# 7seg-weather.net
KiCad netlist of a schematic drawn in EAGLE
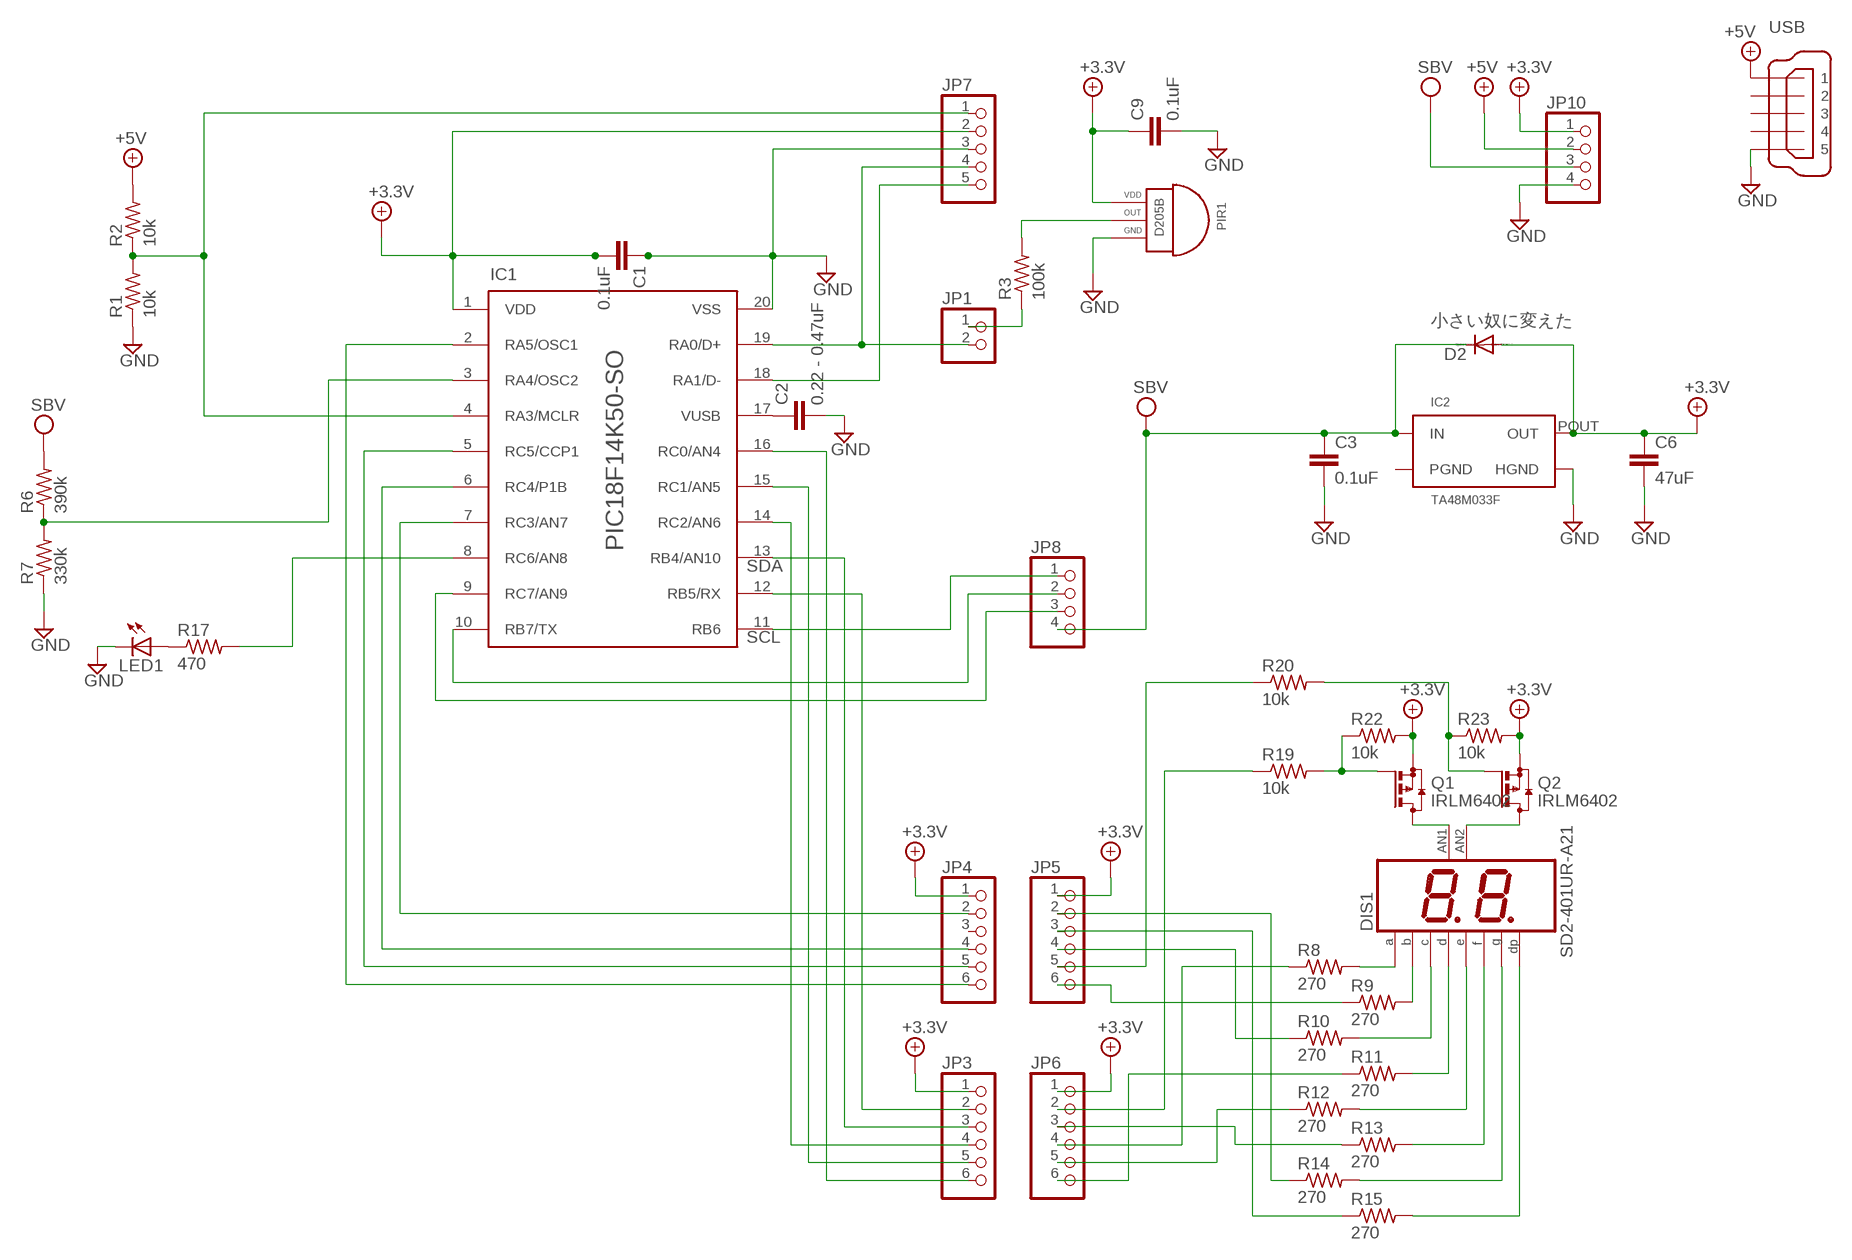
[diagram p0: schematic, sheet 1]

(export (version "E")
  (design (tool "Eeschema 10.0.6"))
  (components
    (comp (ref "C1")
      (value "0.1uF")
      (footprint "eagle-import:C0603K")
      (libsource (lib "eagle-import") (part "C-EUC0603K"))
    )
    (comp (ref "C2")
      (value "0.22 - 0.47uF")
      (footprint "eagle-import:C0603K")
      (libsource (lib "eagle-import") (part "C-EUC0603K"))
    )
    (comp (ref "C3")
      (value "0.1uF")
      (footprint "eagle-import:C0603K")
      (libsource (lib "eagle-import") (part "C-EUC0603K"))
    )
    (comp (ref "C6")
      (value "47uF")
      (footprint "eagle-import:C0603K")
      (libsource (lib "eagle-import") (part "C-EUC0603K"))
    )
    (comp (ref "C9")
      (value "0.1uF")
      (footprint "eagle-import:C0603K")
      (libsource (lib "eagle-import") (part "C-EUC0603K"))
    )
    (comp (ref "D2")
      (value "DIODE-MELF-MLL41")
      (footprint "eagle-import:MELF-MLL41")
      (libsource (lib "eagle-import") (part "DIODE-MELF-MLL41"))
    )
    (comp (ref "DIS1")
      (value "SD2-401UR-A21")
      (footprint "eagle-import:SD2-401UR-A21")
      (libsource (lib "eagle-import") (part "SD2-401UR-A21"))
    )
    (comp (ref "IC1")
      (value "PIC18F14K50-SO")
      (footprint "eagle-import:SO20")
      (libsource (lib "eagle-import") (part "PIC18F14K50-SO"))
    )
    (comp (ref "IC2")
      (value "TA48M033F")
      (footprint "eagle-import:HSOP3")
      (libsource (lib "eagle-import") (part "TA48M033F"))
    )
    (comp (ref "JP1")
      (value "PINHD-1X2")
      (footprint "eagle-import:1X02")
      (libsource (lib "eagle-import") (part "PINHD-1X2"))
    )
    (comp (ref "JP3")
      (value "PINHD-1X6")
      (footprint "eagle-import:1X06")
      (libsource (lib "eagle-import") (part "PINHD-1X6"))
    )
    (comp (ref "JP4")
      (value "PINHD-1X6")
      (footprint "eagle-import:1X06")
      (libsource (lib "eagle-import") (part "PINHD-1X6"))
    )
    (comp (ref "JP5")
      (value "PINHD-1X6")
      (footprint "eagle-import:1X06")
      (libsource (lib "eagle-import") (part "PINHD-1X6"))
    )
    (comp (ref "JP6")
      (value "PINHD-1X6")
      (footprint "eagle-import:1X06")
      (libsource (lib "eagle-import") (part "PINHD-1X6"))
    )
    (comp (ref "JP7")
      (value "PINHD-1X5")
      (footprint "eagle-import:1X05")
      (libsource (lib "eagle-import") (part "PINHD-1X5"))
    )
    (comp (ref "JP8")
      (value "PINHD-1X4")
      (footprint "eagle-import:1X04")
      (libsource (lib "eagle-import") (part "PINHD-1X4"))
    )
    (comp (ref "JP10")
      (value "PINHD-1X4")
      (footprint "eagle-import:1X04")
      (libsource (lib "eagle-import") (part "PINHD-1X4"))
    )
    (comp (ref "LED1")
      (value "LG_T679-E1F1-1")
      (footprint "eagle-import:PLCC2")
      (libsource (lib "eagle-import") (part "_T679-?-1E1F1LG"))
    )
    (comp (ref "PIR1")
      (value "D205B")
      (footprint "eagle-import:3PIN")
      (libsource (lib "eagle-import") (part "D205B"))
    )
    (comp (ref "Q1")
      (value "IRLM6402")
      (footprint "eagle-import:SOT23")
      (libsource (lib "eagle-import") (part "BSS84"))
    )
    (comp (ref "Q2")
      (value "IRLM6402")
      (footprint "eagle-import:SOT23")
      (libsource (lib "eagle-import") (part "BSS84"))
    )
    (comp (ref "R1")
      (value "10k")
      (footprint "eagle-import:M0805")
      (libsource (lib "eagle-import") (part "R-US_M0805"))
    )
    (comp (ref "R2")
      (value "10k")
      (footprint "eagle-import:M0805")
      (libsource (lib "eagle-import") (part "R-US_M0805"))
    )
    (comp (ref "R3")
      (value "100k")
      (footprint "eagle-import:M0805")
      (libsource (lib "eagle-import") (part "R-US_M0805"))
    )
    (comp (ref "R6")
      (value "390k")
      (footprint "eagle-import:M0805")
      (libsource (lib "eagle-import") (part "R-US_M0805"))
    )
    (comp (ref "R7")
      (value "330k")
      (footprint "eagle-import:M0805")
      (libsource (lib "eagle-import") (part "R-US_M0805"))
    )
    (comp (ref "R8")
      (value "270")
      (footprint "eagle-import:M0805")
      (libsource (lib "eagle-import") (part "R-US_M0805"))
    )
    (comp (ref "R9")
      (value "270")
      (footprint "eagle-import:M0805")
      (libsource (lib "eagle-import") (part "resistor_R-US_M0805"))
    )
    (comp (ref "R10")
      (value "270")
      (footprint "eagle-import:M0805")
      (libsource (lib "eagle-import") (part "R-US_M0805"))
    )
    (comp (ref "R11")
      (value "270")
      (footprint "eagle-import:M0805")
      (libsource (lib "eagle-import") (part "R-US_M0805"))
    )
    (comp (ref "R12")
      (value "270")
      (footprint "eagle-import:M0805")
      (libsource (lib "eagle-import") (part "R-US_M0805"))
    )
    (comp (ref "R13")
      (value "270")
      (footprint "eagle-import:M0805")
      (libsource (lib "eagle-import") (part "R-US_M0805"))
    )
    (comp (ref "R14")
      (value "270")
      (footprint "eagle-import:M0805")
      (libsource (lib "eagle-import") (part "R-US_M0805"))
    )
    (comp (ref "R15")
      (value "270")
      (footprint "eagle-import:M0805")
      (libsource (lib "eagle-import") (part "R-US_M0805"))
    )
    (comp (ref "R17")
      (value "470")
      (footprint "eagle-import:M0805")
      (libsource (lib "eagle-import") (part "R-US_M0805"))
    )
    (comp (ref "R19")
      (value "10k")
      (footprint "eagle-import:M0805")
      (libsource (lib "eagle-import") (part "R-US_M0805"))
    )
    (comp (ref "R20")
      (value "10k")
      (footprint "eagle-import:M0805")
      (libsource (lib "eagle-import") (part "R-US_M0805"))
    )
    (comp (ref "R22")
      (value "10k")
      (footprint "eagle-import:M0805")
      (libsource (lib "eagle-import") (part "R-US_M0805"))
    )
    (comp (ref "R23")
      (value "10k")
      (footprint "eagle-import:M0805")
      (libsource (lib "eagle-import") (part "R-US_M0805"))
    )
    (comp (ref "USB")
      (value "MICRO-USB-ZX62R-B-5P")
      (footprint "eagle-import:ZX62R-B-5P")
      (libsource (lib "eagle-import") (part "MICRO-USB-ZX62R-B-5P"))
    )
  )
  (nets
    (net (code "1") (name "+3.3V") (class "Default")
      (node (ref "C1") (pin "2") (pinfunction "2_2") (pintype "passive"))
      (node (ref "C6") (pin "1") (pinfunction "1_1") (pintype "passive"))
      (node (ref "C9") (pin "1") (pinfunction "1_1") (pintype "passive"))
      (node (ref "D2") (pin "A") (pinfunction "A_A") (pintype "passive"))
      (node (ref "IC1") (pin "1") (pinfunction "VDD_1") (pintype "bidirectional"))
      (node (ref "IC2") (pin "POUT") (pinfunction "OUT_POUT") (pintype "power_in"))
      (node (ref "JP10") (pin "1") (pinfunction "1_1") (pintype "passive"))
      (node (ref "JP3") (pin "1") (pinfunction "1_1") (pintype "passive"))
      (node (ref "JP4") (pin "1") (pinfunction "1_1") (pintype "passive"))
      (node (ref "JP5") (pin "1") (pinfunction "1_1") (pintype "passive"))
      (node (ref "JP6") (pin "1") (pinfunction "1_1") (pintype "passive"))
      (node (ref "JP7") (pin "2") (pinfunction "2_2") (pintype "passive"))
      (node (ref "PIR1") (pin "1") (pinfunction "VDD_1") (pintype "bidirectional"))
      (node (ref "Q1") (pin "2") (pinfunction "S_2") (pintype "passive"))
      (node (ref "Q2") (pin "2") (pinfunction "S_2") (pintype "passive"))
      (node (ref "R22") (pin "2") (pinfunction "2_2") (pintype "passive"))
      (node (ref "R23") (pin "2") (pinfunction "2_2") (pintype "passive"))
    )
    (net (code "2") (name "+5V") (class "Default")
      (node (ref "JP10") (pin "2") (pinfunction "2_2") (pintype "passive"))
      (node (ref "R2") (pin "2") (pinfunction "2_2") (pintype "passive"))
      (node (ref "USB") (pin "1") (pinfunction "1_1") (pintype "input"))
    )
    (net (code "3") (name "/PGND") (class "Default")
      (node (ref "IC2") (pin "PGND") (pinfunction "PGND_PGND") (pintype "power_in"))
    )
    (net (code "4") (name "GND") (class "Default")
      (node (ref "C1") (pin "1") (pinfunction "1_1") (pintype "passive"))
      (node (ref "C2") (pin "2") (pinfunction "2_2") (pintype "passive"))
      (node (ref "C3") (pin "2") (pinfunction "2_2") (pintype "passive"))
      (node (ref "C6") (pin "2") (pinfunction "2_2") (pintype "passive"))
      (node (ref "C9") (pin "2") (pinfunction "2_2") (pintype "passive"))
      (node (ref "IC1") (pin "20") (pinfunction "VSS_20") (pintype "bidirectional"))
      (node (ref "IC2") (pin "HGND") (pinfunction "HGND_HGND") (pintype "power_in"))
      (node (ref "JP10") (pin "4") (pinfunction "4_4") (pintype "passive"))
      (node (ref "JP7") (pin "3") (pinfunction "3_3") (pintype "passive"))
      (node (ref "LED1") (pin "C") (pinfunction "C_C") (pintype "passive"))
      (node (ref "PIR1") (pin "3") (pinfunction "GND_3") (pintype "bidirectional"))
      (node (ref "R1") (pin "1") (pinfunction "1_1") (pintype "passive"))
      (node (ref "R7") (pin "1") (pinfunction "1_1") (pintype "passive"))
      (node (ref "USB") (pin "5") (pinfunction "5_5") (pintype "input"))
    )
    (net (code "5") (name "Net-(DIS1-1)") (class "Default")
      (node (ref "DIS1") (pin "P$1") (pinfunction "1_P$1") (pintype "passive"))
      (node (ref "R14") (pin "2") (pinfunction "2_2") (pintype "passive"))
    )
    (net (code "6") (name "Net-(DIS1-2)") (class "Default")
      (node (ref "DIS1") (pin "P$2") (pinfunction "2_P$2") (pintype "passive"))
      (node (ref "R15") (pin "2") (pinfunction "2_2") (pintype "passive"))
    )
    (net (code "7") (name "Net-(DIS1-3)") (class "Default")
      (node (ref "DIS1") (pin "P$3") (pinfunction "3_P$3") (pintype "passive"))
      (node (ref "R8") (pin "2") (pinfunction "2_2") (pintype "passive"))
    )
    (net (code "8") (name "Net-(DIS1-4)") (class "Default")
      (node (ref "DIS1") (pin "P$4") (pinfunction "4_P$4") (pintype "passive"))
      (node (ref "R13") (pin "2") (pinfunction "2_2") (pintype "passive"))
    )
    (net (code "9") (name "Net-(DIS1-5)") (class "Default")
      (node (ref "DIS1") (pin "P$5") (pinfunction "5_P$5") (pintype "passive"))
      (node (ref "Q1") (pin "3") (pinfunction "D_3") (pintype "passive"))
    )
    (net (code "10") (name "Net-(DIS1-6)") (class "Default")
      (node (ref "DIS1") (pin "P$6") (pinfunction "6_P$6") (pintype "passive"))
      (node (ref "R11") (pin "2") (pinfunction "2_2") (pintype "passive"))
    )
    (net (code "11") (name "Net-(DIS1-7)") (class "Default")
      (node (ref "DIS1") (pin "P$7") (pinfunction "7_P$7") (pintype "passive"))
      (node (ref "R12") (pin "2") (pinfunction "2_2") (pintype "passive"))
    )
    (net (code "12") (name "Net-(DIS1-8)") (class "Default")
      (node (ref "DIS1") (pin "P$8") (pinfunction "8_P$8") (pintype "passive"))
      (node (ref "R10") (pin "2") (pinfunction "2_2") (pintype "passive"))
    )
    (net (code "13") (name "Net-(DIS1-9)") (class "Default")
      (node (ref "DIS1") (pin "P$9") (pinfunction "9_P$9") (pintype "passive"))
      (node (ref "R9") (pin "2") (pinfunction "2_2") (pintype "passive"))
    )
    (net (code "14") (name "Net-(DIS1-10)") (class "Default")
      (node (ref "DIS1") (pin "P$10") (pinfunction "10_P$10") (pintype "passive"))
      (node (ref "Q2") (pin "3") (pinfunction "D_3") (pintype "passive"))
    )
    (net (code "15") (name "Net-(IC1-RA0{slash}D+)") (class "Default")
      (node (ref "IC1") (pin "19") (pinfunction "RA0/D+_19") (pintype "bidirectional"))
      (node (ref "JP1") (pin "2") (pinfunction "2_2") (pintype "passive"))
      (node (ref "JP7") (pin "4") (pinfunction "4_4") (pintype "passive"))
    )
    (net (code "16") (name "Net-(IC1-RA1{slash}D-)") (class "Default")
      (node (ref "IC1") (pin "18") (pinfunction "RA1/D-_18") (pintype "bidirectional"))
      (node (ref "JP7") (pin "5") (pinfunction "5_5") (pintype "passive"))
    )
    (net (code "17") (name "Net-(IC1-RA3{slash}MCLR)") (class "Default")
      (node (ref "IC1") (pin "4") (pinfunction "RA3/MCLR_4") (pintype "bidirectional"))
      (node (ref "JP7") (pin "1") (pinfunction "1_1") (pintype "passive"))
      (node (ref "R1") (pin "2") (pinfunction "2_2") (pintype "passive"))
      (node (ref "R2") (pin "1") (pinfunction "1_1") (pintype "passive"))
    )
    (net (code "18") (name "Net-(IC1-RA4{slash}OSC2)") (class "Default")
      (node (ref "IC1") (pin "3") (pinfunction "RA4/OSC2_3") (pintype "bidirectional"))
      (node (ref "R6") (pin "1") (pinfunction "1_1") (pintype "passive"))
      (node (ref "R7") (pin "2") (pinfunction "2_2") (pintype "passive"))
    )
    (net (code "19") (name "Net-(IC1-RA5{slash}OSC1)") (class "Default")
      (node (ref "IC1") (pin "2") (pinfunction "RA5/OSC1_2") (pintype "bidirectional"))
      (node (ref "JP4") (pin "6") (pinfunction "6_6") (pintype "passive"))
    )
    (net (code "20") (name "Net-(IC1-RB4{slash}AN10)") (class "Default")
      (node (ref "IC1") (pin "13") (pinfunction "RB4/AN10_13") (pintype "bidirectional"))
      (node (ref "JP3") (pin "3") (pinfunction "3_3") (pintype "passive"))
    )
    (net (code "21") (name "Net-(IC1-RB5{slash}RX)") (class "Default")
      (node (ref "IC1") (pin "12") (pinfunction "RB5/RX_12") (pintype "bidirectional"))
      (node (ref "JP3") (pin "2") (pinfunction "2_2") (pintype "passive"))
    )
    (net (code "22") (name "Net-(IC1-RB6)") (class "Default")
      (node (ref "IC1") (pin "11") (pinfunction "RB6_11") (pintype "bidirectional"))
      (node (ref "JP8") (pin "1") (pinfunction "1_1") (pintype "passive"))
    )
    (net (code "23") (name "Net-(IC1-RB7{slash}TX)") (class "Default")
      (node (ref "IC1") (pin "10") (pinfunction "RB7/TX_10") (pintype "bidirectional"))
      (node (ref "JP8") (pin "2") (pinfunction "2_2") (pintype "passive"))
    )
    (net (code "24") (name "Net-(IC1-RC0{slash}AN4)") (class "Default")
      (node (ref "IC1") (pin "16") (pinfunction "RC0/AN4_16") (pintype "bidirectional"))
      (node (ref "JP3") (pin "6") (pinfunction "6_6") (pintype "passive"))
    )
    (net (code "25") (name "Net-(IC1-RC1{slash}AN5)") (class "Default")
      (node (ref "IC1") (pin "15") (pinfunction "RC1/AN5_15") (pintype "bidirectional"))
      (node (ref "JP3") (pin "5") (pinfunction "5_5") (pintype "passive"))
    )
    (net (code "26") (name "Net-(IC1-RC2{slash}AN6)") (class "Default")
      (node (ref "IC1") (pin "14") (pinfunction "RC2/AN6_14") (pintype "bidirectional"))
      (node (ref "JP3") (pin "4") (pinfunction "4_4") (pintype "passive"))
    )
    (net (code "27") (name "Net-(IC1-RC3{slash}AN7)") (class "Default")
      (node (ref "IC1") (pin "7") (pinfunction "RC3/AN7_7") (pintype "bidirectional"))
      (node (ref "JP4") (pin "2") (pinfunction "2_2") (pintype "passive"))
    )
    (net (code "28") (name "Net-(IC1-RC4{slash}P1B)") (class "Default")
      (node (ref "IC1") (pin "6") (pinfunction "RC4/P1B_6") (pintype "bidirectional"))
      (node (ref "JP4") (pin "4") (pinfunction "4_4") (pintype "passive"))
    )
    (net (code "29") (name "Net-(IC1-RC5{slash}CCP1)") (class "Default")
      (node (ref "IC1") (pin "5") (pinfunction "RC5/CCP1_5") (pintype "bidirectional"))
      (node (ref "JP4") (pin "5") (pinfunction "5_5") (pintype "passive"))
    )
    (net (code "30") (name "Net-(IC1-RC6{slash}AN8)") (class "Default")
      (node (ref "IC1") (pin "8") (pinfunction "RC6/AN8_8") (pintype "bidirectional"))
      (node (ref "R17") (pin "2") (pinfunction "2_2") (pintype "passive"))
    )
    (net (code "31") (name "Net-(IC1-RC7{slash}AN9)") (class "Default")
      (node (ref "IC1") (pin "9") (pinfunction "RC7/AN9_9") (pintype "bidirectional"))
      (node (ref "JP8") (pin "3") (pinfunction "3_3") (pintype "passive"))
    )
    (net (code "32") (name "Net-(IC1-VUSB)") (class "Default")
      (node (ref "C2") (pin "1") (pinfunction "1_1") (pintype "passive"))
      (node (ref "IC1") (pin "17") (pinfunction "VUSB_17") (pintype "bidirectional"))
    )
    (net (code "33") (name "Net-(JP1-Pad1)") (class "Default")
      (node (ref "JP1") (pin "1") (pinfunction "1_1") (pintype "passive"))
      (node (ref "R3") (pin "1") (pinfunction "1_1") (pintype "passive"))
    )
    (net (code "34") (name "Net-(JP5-Pad2)") (class "Default")
      (node (ref "JP5") (pin "2") (pinfunction "2_2") (pintype "passive"))
      (node (ref "R14") (pin "1") (pinfunction "1_1") (pintype "passive"))
    )
    (net (code "35") (name "Net-(JP5-Pad3)") (class "Default")
      (node (ref "JP5") (pin "3") (pinfunction "3_3") (pintype "passive"))
      (node (ref "R15") (pin "1") (pinfunction "1_1") (pintype "passive"))
    )
    (net (code "36") (name "Net-(JP5-Pad4)") (class "Default")
      (node (ref "JP5") (pin "4") (pinfunction "4_4") (pintype "passive"))
      (node (ref "R10") (pin "1") (pinfunction "1_1") (pintype "passive"))
    )
    (net (code "37") (name "Net-(JP5-Pad5)") (class "Default")
      (node (ref "JP5") (pin "5") (pinfunction "5_5") (pintype "passive"))
      (node (ref "R20") (pin "1") (pinfunction "1_1") (pintype "passive"))
    )
    (net (code "38") (name "Net-(JP5-Pad6)") (class "Default")
      (node (ref "JP5") (pin "6") (pinfunction "6_6") (pintype "passive"))
      (node (ref "R9") (pin "1") (pinfunction "1_1") (pintype "passive"))
    )
    (net (code "39") (name "Net-(JP6-Pad2)") (class "Default")
      (node (ref "JP6") (pin "2") (pinfunction "2_2") (pintype "passive"))
      (node (ref "R19") (pin "1") (pinfunction "1_1") (pintype "passive"))
    )
    (net (code "40") (name "Net-(JP6-Pad3)") (class "Default")
      (node (ref "JP6") (pin "3") (pinfunction "3_3") (pintype "passive"))
      (node (ref "R13") (pin "1") (pinfunction "1_1") (pintype "passive"))
    )
    (net (code "41") (name "Net-(JP6-Pad4)") (class "Default")
      (node (ref "JP6") (pin "4") (pinfunction "4_4") (pintype "passive"))
      (node (ref "R8") (pin "1") (pinfunction "1_1") (pintype "passive"))
    )
    (net (code "42") (name "Net-(JP6-Pad5)") (class "Default")
      (node (ref "JP6") (pin "5") (pinfunction "5_5") (pintype "passive"))
      (node (ref "R12") (pin "1") (pinfunction "1_1") (pintype "passive"))
    )
    (net (code "43") (name "Net-(JP6-Pad6)") (class "Default")
      (node (ref "JP6") (pin "6") (pinfunction "6_6") (pintype "passive"))
      (node (ref "R11") (pin "1") (pinfunction "1_1") (pintype "passive"))
    )
    (net (code "44") (name "Net-(LED1-PadA)") (class "Default")
      (node (ref "LED1") (pin "A") (pinfunction "A_A") (pintype "passive"))
      (node (ref "R17") (pin "1") (pinfunction "1_1") (pintype "passive"))
    )
    (net (code "45") (name "Net-(PIR1-OUT)") (class "Default")
      (node (ref "PIR1") (pin "2") (pinfunction "OUT_2") (pintype "bidirectional"))
      (node (ref "R3") (pin "2") (pinfunction "2_2") (pintype "passive"))
    )
    (net (code "46") (name "Net-(Q1-G)") (class "Default")
      (node (ref "Q1") (pin "1") (pinfunction "G_1") (pintype "passive"))
      (node (ref "R19") (pin "2") (pinfunction "2_2") (pintype "passive"))
      (node (ref "R22") (pin "1") (pinfunction "1_1") (pintype "passive"))
    )
    (net (code "47") (name "Net-(Q2-G)") (class "Default")
      (node (ref "Q2") (pin "1") (pinfunction "G_1") (pintype "passive"))
      (node (ref "R20") (pin "2") (pinfunction "2_2") (pintype "passive"))
      (node (ref "R23") (pin "1") (pinfunction "1_1") (pintype "passive"))
    )
    (net (code "48") (name "SBV") (class "Default")
      (node (ref "C3") (pin "1") (pinfunction "1_1") (pintype "passive"))
      (node (ref "D2") (pin "C") (pinfunction "C_C") (pintype "passive"))
      (node (ref "IC2") (pin "PIN") (pinfunction "IN_PIN") (pintype "power_in"))
      (node (ref "JP10") (pin "3") (pinfunction "3_3") (pintype "passive"))
      (node (ref "JP8") (pin "4") (pinfunction "4_4") (pintype "passive"))
      (node (ref "R6") (pin "2") (pinfunction "2_2") (pintype "passive"))
    )
    (net (code "49") (name "unconnected-(JP4-Pad3)") (class "Default")
      (node (ref "JP4") (pin "3") (pinfunction "3_3") (pintype "passive"))
    )
    (net (code "50") (name "unconnected-(USB-Pad2)") (class "Default")
      (node (ref "USB") (pin "2") (pinfunction "2_2") (pintype "input"))
    )
    (net (code "51") (name "unconnected-(USB-Pad3)") (class "Default")
      (node (ref "USB") (pin "3") (pinfunction "3_3") (pintype "input"))
    )
    (net (code "52") (name "unconnected-(USB-Pad4)") (class "Default")
      (node (ref "USB") (pin "4") (pinfunction "4_4") (pintype "input"))
    )
  )
)
